# simpleCH552_sch_finished.net
KiCad netlist of a schematic drawn in EAGLE
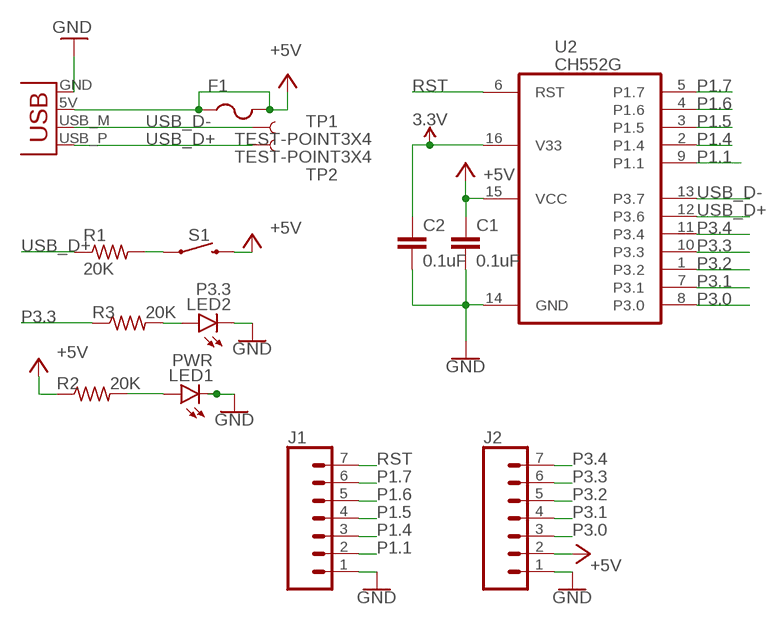
[diagram p0: schematic, sheet 1]

(export (version "E")
  (design (tool "Eeschema 10.0.6"))
  (components
    (comp (ref "C1")
      (value "0.1uF")
      (footprint "eagle-import:C0805K")
      (libsource (lib "eagle-import") (part "C-EUC0805K"))
    )
    (comp (ref "C2")
      (value "0.1uF")
      (footprint "eagle-import:C0805K")
      (libsource (lib "eagle-import") (part "C-EUC0805K"))
    )
    (comp (ref "F1")
      (value "PTCFUSE-1206")
      (footprint "eagle-import:R1206")
      (libsource (lib "eagle-import") (part "PTCFUSE-1206"))
    )
    (comp (ref "J1")
      (value "CONN_07NO_SILK")
      (footprint "eagle-import:1X07_NO_SILK")
      (libsource (lib "eagle-import") (part "CONN_07NO_SILK"))
    )
    (comp (ref "J2")
      (value "CONN_07NO_SILK")
      (footprint "eagle-import:1X07_NO_SILK")
      (libsource (lib "eagle-import") (part "CONN_07NO_SILK"))
    )
    (comp (ref "LED1")
      (value "PWR")
      (footprint "eagle-import:GHI-BASICCOMPONENTS_0805-LED")
      (libsource (lib "eagle-import") (part "GHI-BASICCOMPONENTS_LED-(INCH)-0805"))
    )
    (comp (ref "LED2")
      (value "P3.3")
      (footprint "eagle-import:GHI-BASICCOMPONENTS_0805-LED")
      (libsource (lib "eagle-import") (part "GHI-BASICCOMPONENTS_LED-(INCH)-0805"))
    )
    (comp (ref "R1")
      (value "20K")
      (footprint "eagle-import:R0805")
      (libsource (lib "eagle-import") (part "R-US_R0805"))
    )
    (comp (ref "R2")
      (value "20K")
      (footprint "eagle-import:R0805")
      (libsource (lib "eagle-import") (part "R-US_R0805"))
    )
    (comp (ref "R3")
      (value "20K")
      (footprint "eagle-import:R0805")
      (libsource (lib "eagle-import") (part "R-US_R0805"))
    )
    (comp (ref "S1")
      (value "MOMENTARY-SWITCH-SPST-SMD-6.2MM-TALL")
      (footprint "eagle-import:TACTILE_SWITCH_SMD_6.2MM_TALL")
      (libsource (lib "eagle-import") (part "MOMENTARY-SWITCH-SPST-SMD-6.2MM-TALL"))
    )
    (comp (ref "TP1")
      (value "TEST-POINT3X4")
      (footprint "eagle-import:PAD.03X.04")
      (libsource (lib "eagle-import") (part "TEST-POINT3X4"))
    )
    (comp (ref "TP2")
      (value "TEST-POINT3X4")
      (footprint "eagle-import:PAD.03X.04")
      (libsource (lib "eagle-import") (part "TEST-POINT3X4"))
    )
    (comp (ref "U2")
      (value "CH552G")
      (footprint "eagle-import:MY_IC_SO16")
      (libsource (lib "eagle-import") (part "MY_IC_CH551G_CH552GSOP-16"))
    )
    (comp (ref "X1")
      (value "USBPCB")
      (footprint "eagle-import:USB-A-PCB")
      (libsource (lib "eagle-import") (part "USBPCB"))
    )
  )
  (nets
    (net (code "1") (name "+5V") (class "Default")
      (node (ref "C1") (pin "1") (pinfunction "1_1") (pintype "passive"))
      (node (ref "F1") (pin "1") (pinfunction "1_1") (pintype "passive"))
      (node (ref "F1") (pin "2") (pinfunction "2_2") (pintype "passive"))
      (node (ref "J2") (pin "2") (pinfunction "2_2") (pintype "passive"))
      (node (ref "R2") (pin "1") (pinfunction "1_1") (pintype "passive"))
      (node (ref "S1") (pin "B2") (pinfunction "2_B2") (pintype "passive"))
      (node (ref "U2") (pin "15") (pinfunction "VCC_15") (pintype "power_in"))
      (node (ref "X1") (pin "5V") (pinfunction "VBUS_5V") (pintype "bidirectional"))
    )
    (net (code "2") (name "/P1.1") (class "Default")
      (node (ref "J1") (pin "2") (pinfunction "2_2") (pintype "passive"))
      (node (ref "U2") (pin "9") (pinfunction "P1.1_9") (pintype "bidirectional"))
    )
    (net (code "3") (name "/P1.4") (class "Default")
      (node (ref "J1") (pin "3") (pinfunction "3_3") (pintype "passive"))
      (node (ref "U2") (pin "2") (pinfunction "P1.4_2") (pintype "bidirectional"))
    )
    (net (code "4") (name "/P1.5") (class "Default")
      (node (ref "J1") (pin "4") (pinfunction "4_4") (pintype "passive"))
      (node (ref "U2") (pin "3") (pinfunction "P1.5_3") (pintype "bidirectional"))
    )
    (net (code "5") (name "/P1.6") (class "Default")
      (node (ref "J1") (pin "5") (pinfunction "5_5") (pintype "passive"))
      (node (ref "U2") (pin "4") (pinfunction "P1.6_4") (pintype "bidirectional"))
    )
    (net (code "6") (name "/P1.7") (class "Default")
      (node (ref "J1") (pin "6") (pinfunction "6_6") (pintype "passive"))
      (node (ref "U2") (pin "5") (pinfunction "P1.7_5") (pintype "bidirectional"))
    )
    (net (code "7") (name "/P3.0") (class "Default")
      (node (ref "J2") (pin "3") (pinfunction "3_3") (pintype "passive"))
      (node (ref "U2") (pin "8") (pinfunction "P3.0_8") (pintype "bidirectional"))
    )
    (net (code "8") (name "/P3.1") (class "Default")
      (node (ref "J2") (pin "4") (pinfunction "4_4") (pintype "passive"))
      (node (ref "U2") (pin "7") (pinfunction "P3.1_7") (pintype "bidirectional"))
    )
    (net (code "9") (name "/P3.2") (class "Default")
      (node (ref "J2") (pin "5") (pinfunction "5_5") (pintype "passive"))
      (node (ref "U2") (pin "1") (pinfunction "P3.2_1") (pintype "bidirectional"))
    )
    (net (code "10") (name "/P3.3") (class "Default")
      (node (ref "J2") (pin "6") (pinfunction "6_6") (pintype "passive"))
      (node (ref "R3") (pin "1") (pinfunction "1_1") (pintype "passive"))
      (node (ref "U2") (pin "10") (pinfunction "P3.3_10") (pintype "bidirectional"))
    )
    (net (code "11") (name "/P3.4") (class "Default")
      (node (ref "J2") (pin "7") (pinfunction "7_7") (pintype "passive"))
      (node (ref "U2") (pin "11") (pinfunction "P3.4_11") (pintype "bidirectional"))
    )
    (net (code "12") (name "/RST") (class "Default")
      (node (ref "J1") (pin "7") (pinfunction "7_7") (pintype "passive"))
      (node (ref "U2") (pin "6") (pinfunction "RST_6") (pintype "input"))
    )
    (net (code "13") (name "/USB_D+") (class "Default")
      (node (ref "R1") (pin "1") (pinfunction "1_1") (pintype "passive"))
      (node (ref "TP2") (pin "P$1") (pinfunction "1_P$1") (pintype "bidirectional"))
      (node (ref "U2") (pin "12") (pinfunction "P3.6_12") (pintype "bidirectional"))
      (node (ref "X1") (pin "USB_P") (pinfunction "D+_USB_P") (pintype "bidirectional"))
    )
    (net (code "14") (name "/USB_D-") (class "Default")
      (node (ref "TP1") (pin "P$1") (pinfunction "1_P$1") (pintype "bidirectional"))
      (node (ref "U2") (pin "13") (pinfunction "P3.7_13") (pintype "bidirectional"))
      (node (ref "X1") (pin "USB_M") (pinfunction "D-_USB_M") (pintype "bidirectional"))
    )
    (net (code "15") (name "3.3V") (class "Default")
      (node (ref "C2") (pin "1") (pinfunction "1_1") (pintype "passive"))
      (node (ref "U2") (pin "16") (pinfunction "V33_16") (pintype "power_in"))
    )
    (net (code "16") (name "GND") (class "Default")
      (node (ref "C1") (pin "2") (pinfunction "2_2") (pintype "passive"))
      (node (ref "C2") (pin "2") (pinfunction "2_2") (pintype "passive"))
      (node (ref "J1") (pin "1") (pinfunction "1_1") (pintype "passive"))
      (node (ref "J2") (pin "1") (pinfunction "1_1") (pintype "passive"))
      (node (ref "LED1") (pin "K") (pinfunction "K_K") (pintype "passive"))
      (node (ref "LED2") (pin "K") (pinfunction "K_K") (pintype "passive"))
      (node (ref "U2") (pin "14") (pinfunction "GND_14") (pintype "power_in"))
      (node (ref "X1") (pin "GND") (pinfunction "GND_GND") (pintype "bidirectional"))
    )
    (net (code "17") (name "Net-(LED1-PadA)") (class "Default")
      (node (ref "LED1") (pin "A") (pinfunction "A_A") (pintype "passive"))
      (node (ref "R2") (pin "2") (pinfunction "2_2") (pintype "passive"))
    )
    (net (code "18") (name "Net-(LED2-PadA)") (class "Default")
      (node (ref "LED2") (pin "A") (pinfunction "A_A") (pintype "passive"))
      (node (ref "R3") (pin "2") (pinfunction "2_2") (pintype "passive"))
    )
    (net (code "19") (name "Net-(S1-1)") (class "Default")
      (node (ref "R1") (pin "2") (pinfunction "2_2") (pintype "passive"))
      (node (ref "S1") (pin "A2") (pinfunction "1_A2") (pintype "passive"))
    )
  )
)
